# Putri_Shaqila_GT4.net
KiCad netlist of a schematic drawn in EAGLE
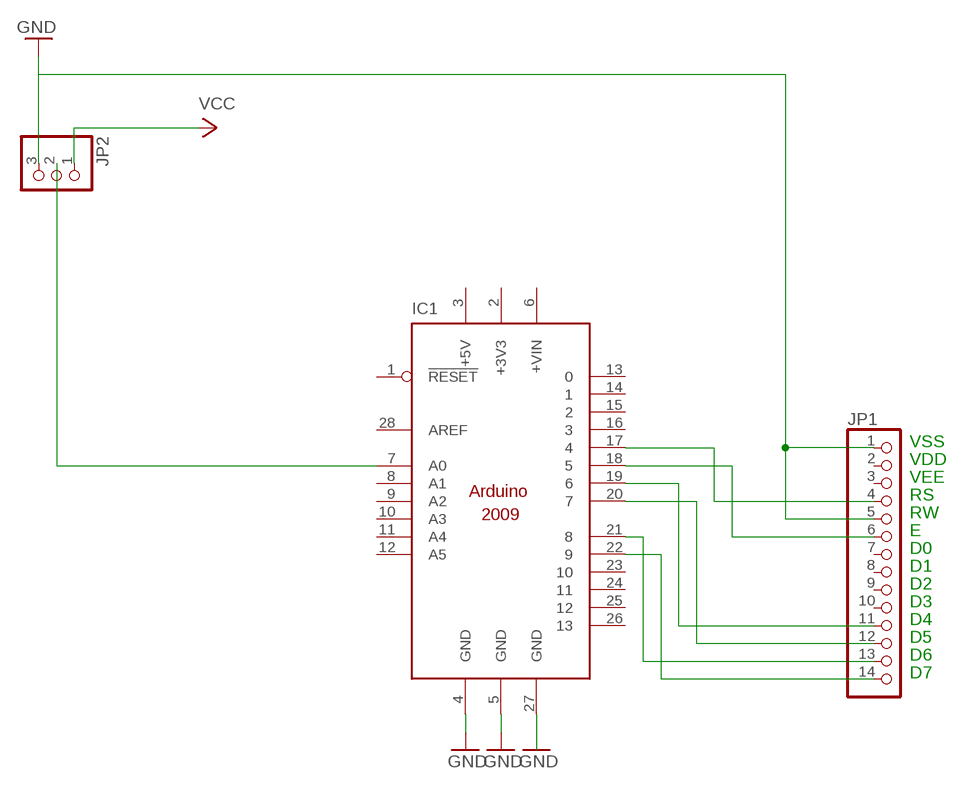
[diagram p0: schematic, sheet 1]

(export (version "E")
  (design (tool "Eeschema 10.0.6"))
  (components
    (comp (ref "IC1")
      (value "ARDUINO2009_12")
      (footprint "eagle-import:ARDUINO2009_2")
      (libsource (lib "eagle-import") (part "ARDUINO2009_12"))
    )
    (comp (ref "JP1")
      (value "PINHD-1X14")
      (footprint "eagle-import:1X14")
      (libsource (lib "eagle-import") (part "PINHD-1X14"))
    )
    (comp (ref "JP2")
      (value "PINHD-1X3")
      (footprint "eagle-import:1X03")
      (libsource (lib "eagle-import") (part "PINHD-1X3"))
    )
  )
  (nets
    (net (code "1") (name "/+3V3") (class "Default")
      (node (ref "IC1") (pin "2") (pinfunction "+3V3_2") (pintype "power_in"))
    )
    (net (code "2") (name "/+5V") (class "Default")
      (node (ref "IC1") (pin "3") (pinfunction "+5V_3") (pintype "power_in"))
    )
    (net (code "3") (name "GND") (class "Default")
      (node (ref "IC1") (pin "4") (pinfunction "GND_4") (pintype "power_in"))
      (node (ref "IC1") (pin "5") (pinfunction "GND_5") (pintype "power_in"))
      (node (ref "JP2") (pin "3") (pinfunction "3_3") (pintype "passive"))
    )
    (net (code "4") (name "Net-(IC1-4)") (class "Default")
      (node (ref "IC1") (pin "17") (pinfunction "4_17") (pintype "bidirectional"))
      (node (ref "JP1") (pin "4") (pinfunction "4_4") (pintype "passive"))
    )
    (net (code "5") (name "Net-(IC1-5)") (class "Default")
      (node (ref "IC1") (pin "18") (pinfunction "5_18") (pintype "bidirectional"))
      (node (ref "JP1") (pin "6") (pinfunction "6_6") (pintype "passive"))
    )
    (net (code "6") (name "Net-(IC1-6)") (class "Default")
      (node (ref "IC1") (pin "19") (pinfunction "6_19") (pintype "bidirectional"))
      (node (ref "JP1") (pin "11") (pinfunction "11_11") (pintype "passive"))
    )
    (net (code "7") (name "Net-(IC1-7)") (class "Default")
      (node (ref "IC1") (pin "20") (pinfunction "7_20") (pintype "bidirectional"))
      (node (ref "JP1") (pin "12") (pinfunction "12_12") (pintype "passive"))
    )
    (net (code "8") (name "Net-(IC1-8)") (class "Default")
      (node (ref "IC1") (pin "21") (pinfunction "8_21") (pintype "bidirectional"))
      (node (ref "JP1") (pin "13") (pinfunction "13_13") (pintype "passive"))
    )
    (net (code "9") (name "Net-(IC1-9)") (class "Default")
      (node (ref "IC1") (pin "22") (pinfunction "9_22") (pintype "bidirectional"))
      (node (ref "JP1") (pin "14") (pinfunction "14_14") (pintype "passive"))
    )
    (net (code "10") (name "Net-(IC1-A0)") (class "Default")
      (node (ref "IC1") (pin "7") (pinfunction "A0_7") (pintype "bidirectional"))
      (node (ref "JP2") (pin "2") (pinfunction "2_2") (pintype "passive"))
    )
    (net (code "11") (name "Net-(JP1-Pad1)") (class "Default")
      (node (ref "JP1") (pin "1") (pinfunction "1_1") (pintype "passive"))
      (node (ref "JP1") (pin "5") (pinfunction "5_5") (pintype "passive"))
    )
    (net (code "12") (name "VCC") (class "Default")
      (node (ref "JP2") (pin "1") (pinfunction "1_1") (pintype "passive"))
    )
    (net (code "13") (name "unconnected-(IC1-+VIN-Pad6)") (class "Default")
      (node (ref "IC1") (pin "6") (pinfunction "+VIN_6") (pintype "bidirectional"))
    )
    (net (code "14") (name "unconnected-(IC1-0-Pad13)") (class "Default")
      (node (ref "IC1") (pin "13") (pinfunction "0_13") (pintype "bidirectional"))
    )
    (net (code "15") (name "unconnected-(IC1-1-Pad14)") (class "Default")
      (node (ref "IC1") (pin "14") (pinfunction "1_14") (pintype "bidirectional"))
    )
    (net (code "16") (name "unconnected-(IC1-2-Pad15)") (class "Default")
      (node (ref "IC1") (pin "15") (pinfunction "2_15") (pintype "bidirectional"))
    )
    (net (code "17") (name "unconnected-(IC1-3-Pad16)") (class "Default")
      (node (ref "IC1") (pin "16") (pinfunction "3_16") (pintype "bidirectional"))
    )
    (net (code "18") (name "unconnected-(IC1-10-Pad23)") (class "Default")
      (node (ref "IC1") (pin "23") (pinfunction "10_23") (pintype "bidirectional"))
    )
    (net (code "19") (name "unconnected-(IC1-11-Pad24)") (class "Default")
      (node (ref "IC1") (pin "24") (pinfunction "11_24") (pintype "bidirectional"))
    )
    (net (code "20") (name "unconnected-(IC1-12-Pad25)") (class "Default")
      (node (ref "IC1") (pin "25") (pinfunction "12_25") (pintype "bidirectional"))
    )
    (net (code "21") (name "unconnected-(IC1-13-Pad26)") (class "Default")
      (node (ref "IC1") (pin "26") (pinfunction "13_26") (pintype "bidirectional"))
    )
    (net (code "22") (name "unconnected-(IC1-A1-Pad8)") (class "Default")
      (node (ref "IC1") (pin "8") (pinfunction "A1_8") (pintype "bidirectional"))
    )
    (net (code "23") (name "unconnected-(IC1-A2-Pad9)") (class "Default")
      (node (ref "IC1") (pin "9") (pinfunction "A2_9") (pintype "bidirectional"))
    )
    (net (code "24") (name "unconnected-(IC1-A3-Pad10)") (class "Default")
      (node (ref "IC1") (pin "10") (pinfunction "A3_10") (pintype "bidirectional"))
    )
    (net (code "25") (name "unconnected-(IC1-A4-Pad11)") (class "Default")
      (node (ref "IC1") (pin "11") (pinfunction "A4_11") (pintype "bidirectional"))
    )
    (net (code "26") (name "unconnected-(IC1-A5-Pad12)") (class "Default")
      (node (ref "IC1") (pin "12") (pinfunction "A5_12") (pintype "bidirectional"))
    )
    (net (code "27") (name "unconnected-(IC1-AREF-Pad28)") (class "Default")
      (node (ref "IC1") (pin "28") (pinfunction "AREF_28") (pintype "bidirectional"))
    )
    (net (code "28") (name "unconnected-(IC1-GND-Pad27)") (class "Default")
      (node (ref "IC1") (pin "27") (pinfunction "GND_27") (pintype "power_in"))
    )
    (net (code "29") (name "unconnected-(IC1-~{RESET}-Pad1)") (class "Default")
      (node (ref "IC1") (pin "1") (pinfunction "~{RESET}_1") (pintype "bidirectional"))
    )
    (net (code "30") (name "unconnected-(JP1-Pad2)") (class "Default")
      (node (ref "JP1") (pin "2") (pinfunction "2_2") (pintype "passive"))
    )
    (net (code "31") (name "unconnected-(JP1-Pad3)") (class "Default")
      (node (ref "JP1") (pin "3") (pinfunction "3_3") (pintype "passive"))
    )
    (net (code "32") (name "unconnected-(JP1-Pad7)") (class "Default")
      (node (ref "JP1") (pin "7") (pinfunction "7_7") (pintype "passive"))
    )
    (net (code "33") (name "unconnected-(JP1-Pad8)") (class "Default")
      (node (ref "JP1") (pin "8") (pinfunction "8_8") (pintype "passive"))
    )
    (net (code "34") (name "unconnected-(JP1-Pad9)") (class "Default")
      (node (ref "JP1") (pin "9") (pinfunction "9_9") (pintype "passive"))
    )
    (net (code "35") (name "unconnected-(JP1-Pad10)") (class "Default")
      (node (ref "JP1") (pin "10") (pinfunction "10_10") (pintype "passive"))
    )
  )
)
